# Power_VIN_5v_LM1117.net
KiCad netlist of a schematic drawn in EAGLE
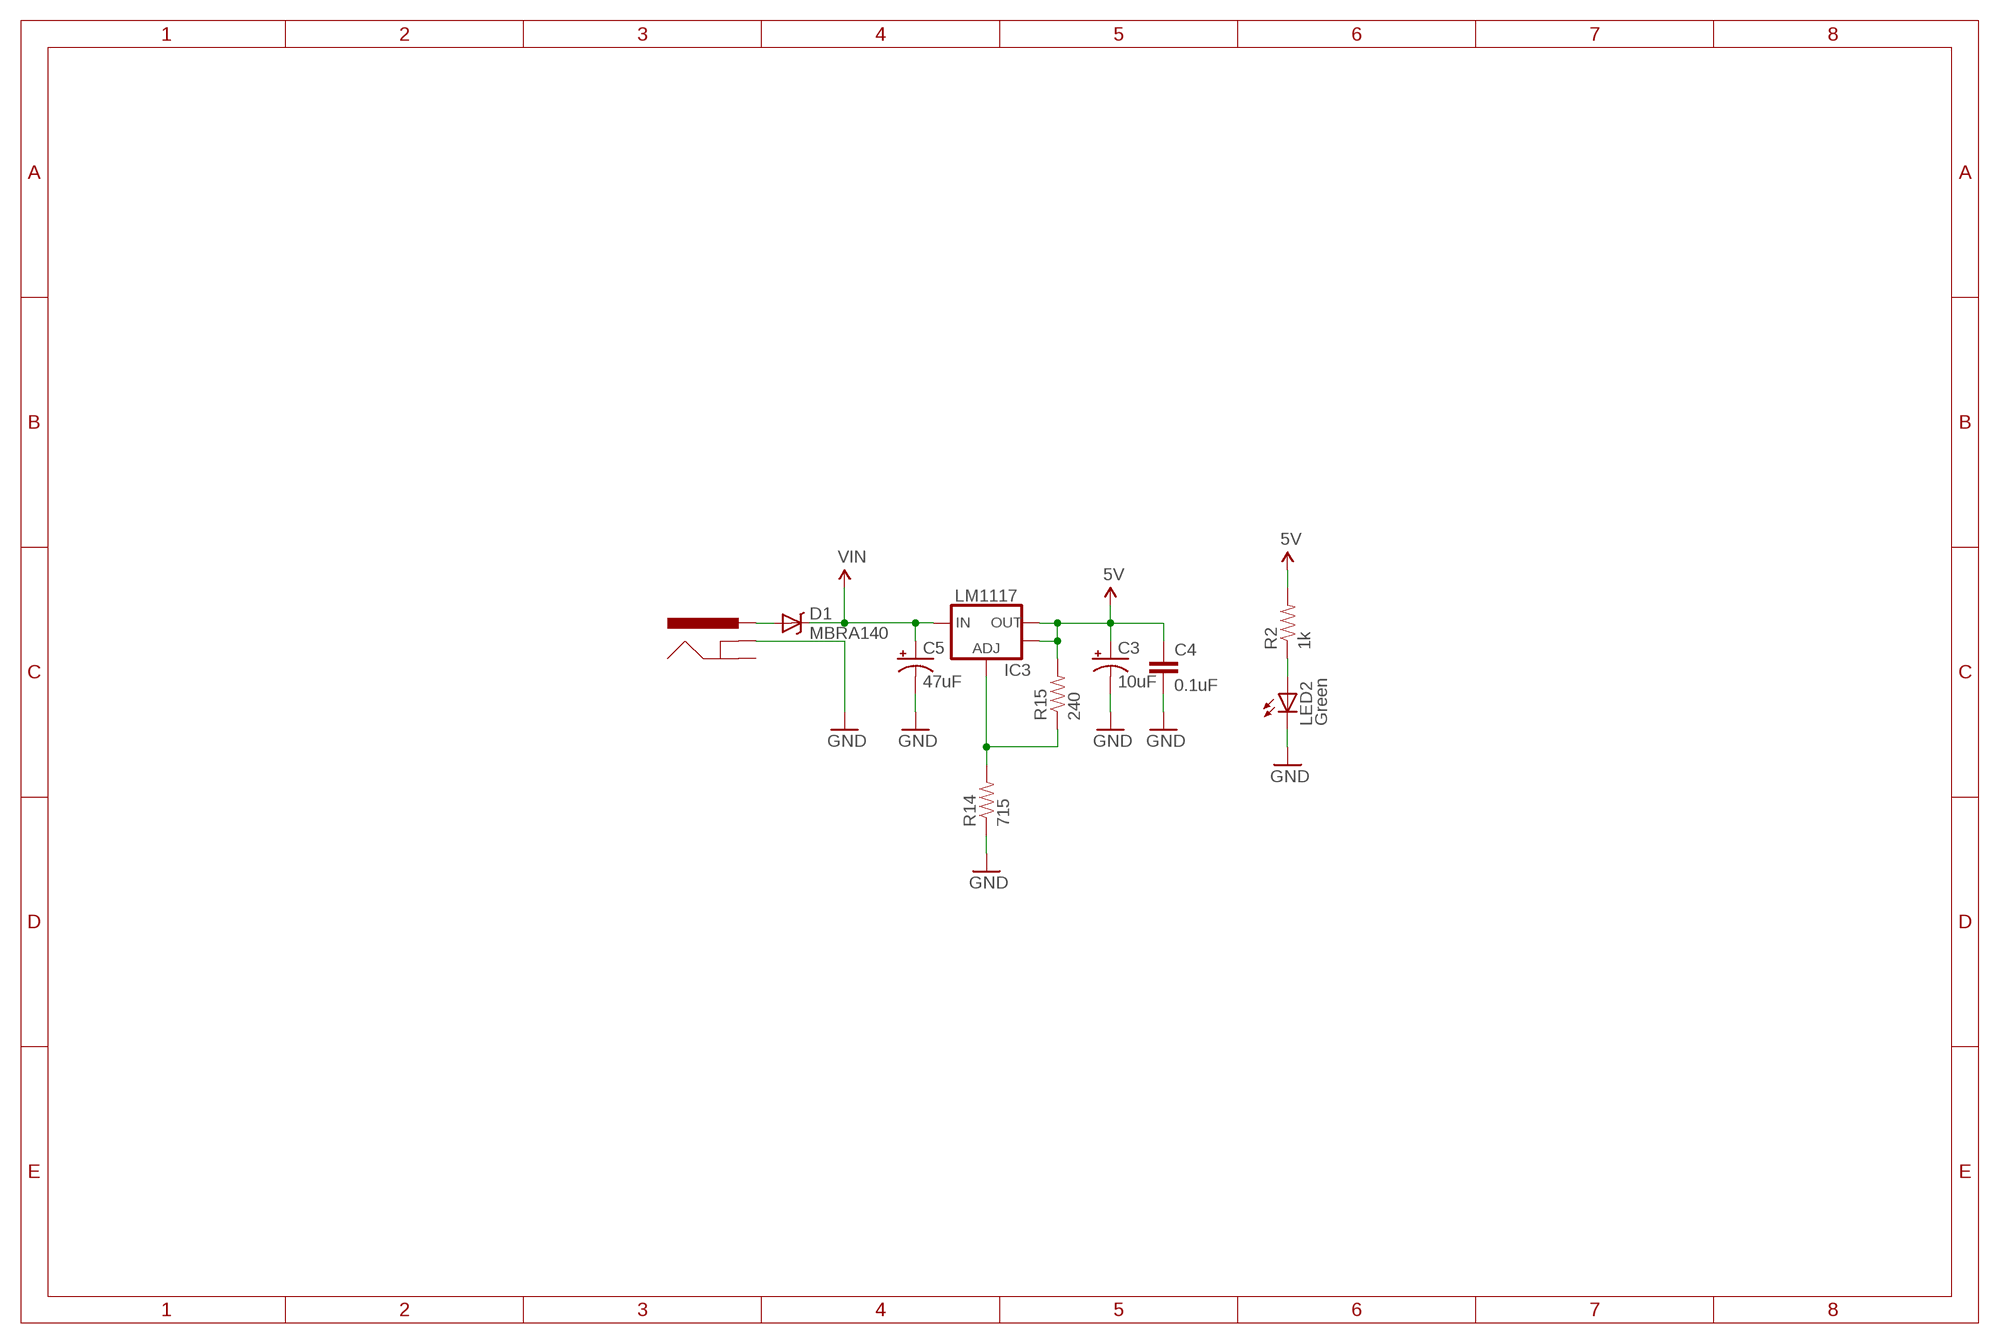
[diagram p0: schematic, sheet 1]

(export (version "E")
  (design (tool "Eeschema 10.0.6"))
  (components
    (comp (ref "C3")
      (value "10uF")
      (footprint "eagle-import:EIA3216")
      (libsource (lib "eagle-import") (part "CAP_POL1206"))
    )
    (comp (ref "C4")
      (value "0.1uF")
      (footprint "eagle-import:0603-CAP")
      (libsource (lib "eagle-import") (part "CAP0603-CAP"))
    )
    (comp (ref "C5")
      (value "47uF")
      (footprint "eagle-import:PANASONIC_D")
      (libsource (lib "eagle-import") (part "CAP_POLD"))
    )
    (comp (ref "D1")
      (value "MBRA140")
      (footprint "eagle-import:SMA-DIODE")
      (libsource (lib "eagle-import") (part "DIODE-SCHOTTKY_"))
    )
    (comp (ref "IC3")
      (value "LM1117")
      (footprint "eagle-import:SOT223-ALT1")
      (libsource (lib "eagle-import") (part "V_REG_LM1117ALT1"))
    )
    (comp (ref "J1")
      (value "POWER_JACKOVERPASTE_REDBOARD_0603")
      (footprint "eagle-import:POWER_JACK_SMD_OVERPASTE_REDBOARD_0603")
      (libsource (lib "eagle-import") (part "POWER_JACKOVERPASTE_REDBOARD_0603"))
    )
    (comp (ref "LED2")
      (value "Green")
      (footprint "eagle-import:LED-1206-NO_SILK")
      (libsource (lib "eagle-import") (part "LED1206-NS"))
    )
    (comp (ref "R2")
      (value "1k")
      (footprint "eagle-import:0603-RES")
      (libsource (lib "eagle-import") (part "RESISTOR0603-RES"))
    )
    (comp (ref "R14")
      (value "715")
      (footprint "eagle-import:0603-RES")
      (libsource (lib "eagle-import") (part "RESISTOR0603-RES"))
    )
    (comp (ref "R15")
      (value "240")
      (footprint "eagle-import:0603-RES")
      (libsource (lib "eagle-import") (part "RESISTOR0603-RES"))
    )
  )
  (nets
    (net (code "1") (name "5V") (class "Default")
      (node (ref "C3") (pin "A") (pinfunction "+_A") (pintype "passive"))
      (node (ref "C4") (pin "1") (pinfunction "1_1") (pintype "passive"))
      (node (ref "IC3") (pin "2") (pinfunction "OUT_2") (pintype "output"))
      (node (ref "IC3") (pin "4") (pinfunction "OUT_4") (pintype "output"))
      (node (ref "R15") (pin "2") (pinfunction "2_2") (pintype "passive"))
      (node (ref "R2") (pin "2") (pinfunction "2_2") (pintype "passive"))
    )
    (net (code "2") (name "GND") (class "Default")
      (node (ref "C3") (pin "C") (pinfunction "-_C") (pintype "passive"))
      (node (ref "C4") (pin "2") (pinfunction "2_2") (pintype "passive"))
      (node (ref "C5") (pin "-") (pinfunction "-_-") (pintype "passive"))
      (node (ref "J1") (pin "GND") (pinfunction "GNDBREAK_GND") (pintype "bidirectional"))
      (node (ref "LED2") (pin "C") (pinfunction "C_C") (pintype "passive"))
      (node (ref "R14") (pin "1") (pinfunction "1_1") (pintype "passive"))
    )
    (net (code "3") (name "Net-(IC3-ADJ)") (class "Default")
      (node (ref "IC3") (pin "1") (pinfunction "ADJ_1") (pintype "input"))
      (node (ref "R14") (pin "2") (pinfunction "2_2") (pintype "passive"))
      (node (ref "R15") (pin "1") (pinfunction "1_1") (pintype "passive"))
    )
    (net (code "4") (name "Net-(J1-PWR)") (class "Default")
      (node (ref "D1") (pin "A") (pinfunction "A_A") (pintype "passive"))
      (node (ref "J1") (pin "VIN0") (pinfunction "PWR_VIN0") (pintype "bidirectional"))
    )
    (net (code "5") (name "Net-(LED2-PadA)") (class "Default")
      (node (ref "LED2") (pin "A") (pinfunction "A_A") (pintype "passive"))
      (node (ref "R2") (pin "1") (pinfunction "1_1") (pintype "passive"))
    )
    (net (code "6") (name "VIN") (class "Default")
      (node (ref "C5") (pin "+") (pinfunction "+_+") (pintype "passive"))
      (node (ref "D1") (pin "C") (pinfunction "C_C") (pintype "passive"))
      (node (ref "IC3") (pin "3") (pinfunction "IN_3") (pintype "input"))
    )
    (net (code "7") (name "unconnected-(J1-GND-PadP$4)") (class "Default")
      (node (ref "J1") (pin "P$4") (pinfunction "GND_P$4") (pintype "bidirectional"))
    )
  )
)
